# schematic_without_jumperlable.net
KiCad netlist of a schematic drawn in EAGLE
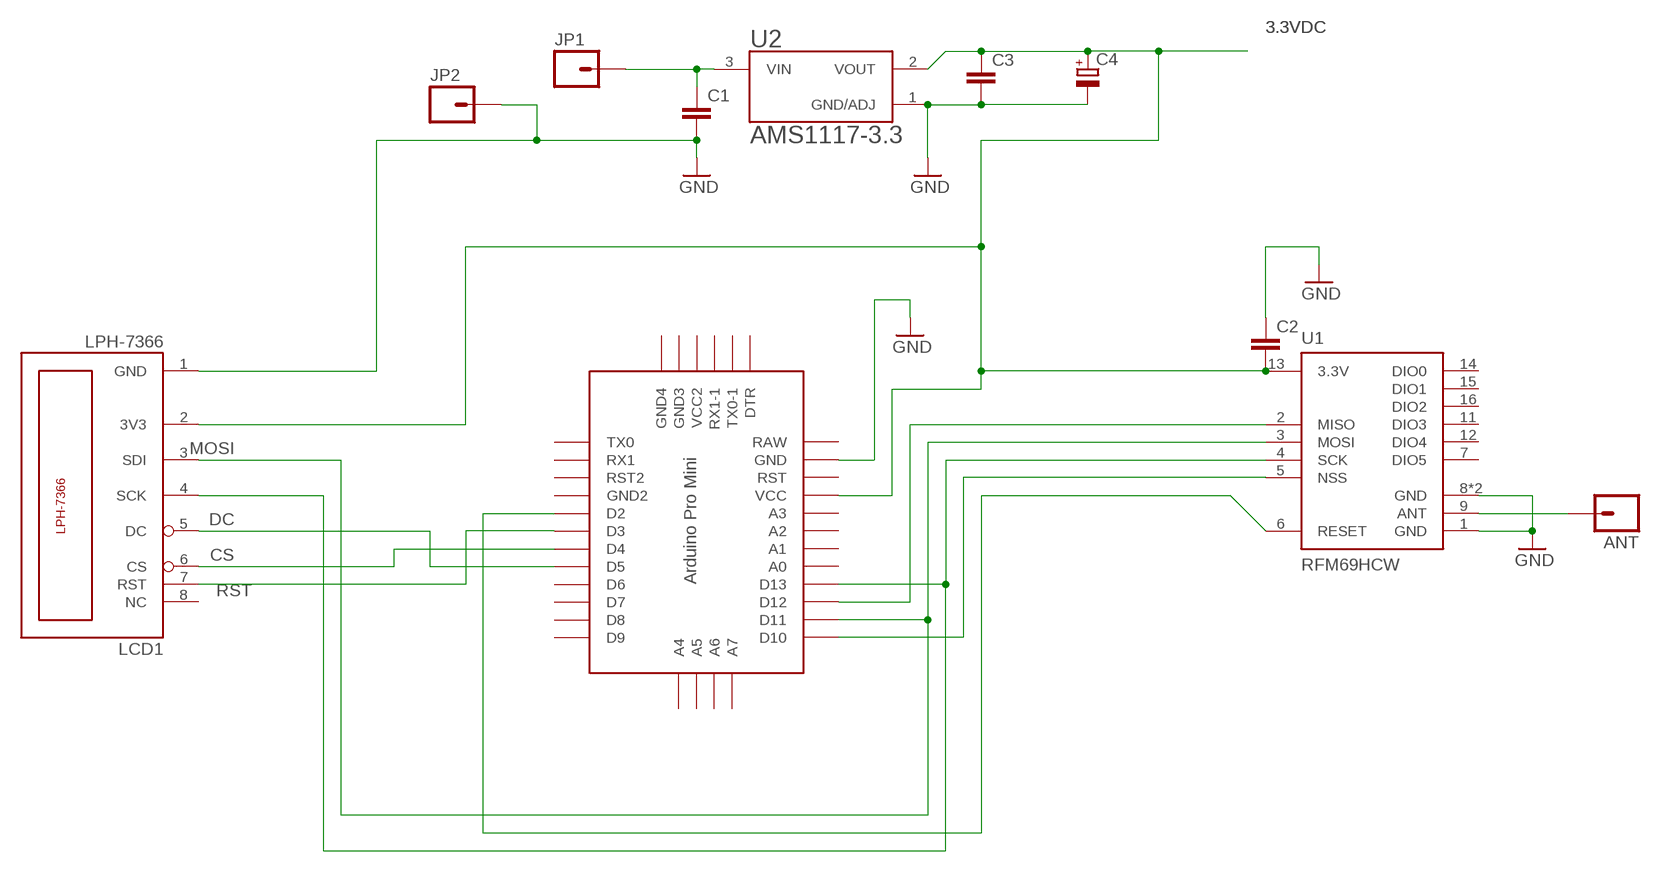
[diagram p0: schematic, sheet 1]

(export (version "E")
  (design (tool "Eeschema 10.0.6"))
  (components
    (comp (ref "ANT")
      (value "M01SMDNS")
      (footprint "eagle-import:1X01NS")
      (libsource (lib "eagle-import") (part "M01SMDNS"))
    )
    (comp (ref "C1")
      (value "C-EU025-030X050")
      (footprint "eagle-import:C025-030X050")
      (libsource (lib "eagle-import") (part "C-EU025-030X050"))
    )
    (comp (ref "C2")
      (value "C-EU025-030X050")
      (footprint "eagle-import:C025-030X050")
      (libsource (lib "eagle-import") (part "C-EU025-030X050"))
    )
    (comp (ref "C3")
      (value "C-EU025-030X050")
      (footprint "eagle-import:C025-030X050")
      (libsource (lib "eagle-import") (part "C-EU025-030X050"))
    )
    (comp (ref "C4")
      (value "CPOL-EUE5-8.5")
      (footprint "eagle-import:E5-8,5")
      (libsource (lib "eagle-import") (part "CPOL-EUE5-8.5"))
    )
    (comp (ref "JP1")
      (value "M01SMDNS")
      (footprint "eagle-import:1X01NS")
      (libsource (lib "eagle-import") (part "M01SMDNS"))
    )
    (comp (ref "JP2")
      (value "M01SMDNS")
      (footprint "eagle-import:1X01NS")
      (libsource (lib "eagle-import") (part "M01SMDNS"))
    )
    (comp (ref "LCD1")
      (value "LPH-7366")
      (footprint "eagle-import:LPH-7366")
      (libsource (lib "eagle-import") (part "LPH-7366"))
    )
    (comp (ref "U$1")
      (value "PRO-MINI")
      (footprint "eagle-import:PRO-MINI")
      (libsource (lib "eagle-import") (part "PRO-MINI"))
    )
    (comp (ref "U1")
      (value "RFM69HCW")
      (footprint "eagle-import:RFM69HCW-XXXS2")
      (libsource (lib "eagle-import") (part "RFM69HCW"))
    )
    (comp (ref "U2")
      (value "AMS1117-3.3")
      (footprint "eagle-import:SOT229P700X180-4N")
      (fields (field (name "MF") "Advanced Monolithic Systems"))
      (libsource (lib "eagle-import") (part "AMS1117-3.3"))
    )
  )
  (nets
    (net (code "1") (name "/3.3VDC") (class "Default")
      (node (ref "C2") (pin "2") (pinfunction "2_2") (pintype "passive"))
      (node (ref "C3") (pin "1") (pinfunction "1_1") (pintype "passive"))
      (node (ref "C4") (pin "+") (pinfunction "+_+") (pintype "passive"))
      (node (ref "LCD1") (pin "2") (pinfunction "3V3_2") (pintype "power_in"))
      (node (ref "U$1") (pin "VCC") (pinfunction "VCC_VCC") (pintype "bidirectional"))
      (node (ref "U1") (pin "13") (pinfunction "3.3V_13") (pintype "power_in"))
      (node (ref "U2") (pin "2") (pinfunction "VOUT_2") (pintype "output"))
    )
    (net (code "2") (name "/CS") (class "Default")
      (node (ref "LCD1") (pin "6") (pinfunction "CS_6") (pintype "input"))
      (node (ref "U$1") (pin "D4") (pinfunction "D4_D4") (pintype "bidirectional"))
    )
    (net (code "3") (name "/DC") (class "Default")
      (node (ref "LCD1") (pin "5") (pinfunction "DC_5") (pintype "input"))
      (node (ref "U$1") (pin "D5") (pinfunction "D5_D5") (pintype "bidirectional"))
    )
    (net (code "4") (name "/MOSI") (class "Default")
      (node (ref "LCD1") (pin "3") (pinfunction "SDI_3") (pintype "power_in"))
      (node (ref "U$1") (pin "D11") (pinfunction "D11_D11") (pintype "bidirectional"))
      (node (ref "U1") (pin "3") (pinfunction "MOSI_3") (pintype "input"))
    )
    (net (code "5") (name "/RAW") (class "Default")
      (node (ref "U$1") (pin "RAW") (pinfunction "RAW_RAW") (pintype "power_in"))
    )
    (net (code "6") (name "/RST") (class "Default")
      (node (ref "LCD1") (pin "7") (pinfunction "RST_7") (pintype "input"))
      (node (ref "U$1") (pin "D3") (pinfunction "D3_D3") (pintype "bidirectional"))
    )
    (net (code "7") (name "GND") (class "Default")
      (node (ref "C1") (pin "2") (pinfunction "2_2") (pintype "passive"))
      (node (ref "C2") (pin "1") (pinfunction "1_1") (pintype "passive"))
      (node (ref "C3") (pin "2") (pinfunction "2_2") (pintype "passive"))
      (node (ref "C4") (pin "-") (pinfunction "-_-") (pintype "passive"))
      (node (ref "JP2") (pin "1") (pinfunction "1_1") (pintype "passive"))
      (node (ref "LCD1") (pin "1") (pinfunction "GND_1") (pintype "power_in"))
      (node (ref "U$1") (pin "GND") (pinfunction "GND_GND") (pintype "input"))
      (node (ref "U1") (pin "1") (pinfunction "GND_1") (pintype "power_in"))
      (node (ref "U1") (pin "10") (pinfunction "GND_10") (pintype "power_in"))
      (node (ref "U1") (pin "8") (pinfunction "GND_8") (pintype "power_in"))
      (node (ref "U2") (pin "1") (pinfunction "GND/ADJ_1") (pintype "power_in"))
    )
    (net (code "8") (name "Net-(LCD1-SCK)") (class "Default")
      (node (ref "LCD1") (pin "4") (pinfunction "SCK_4") (pintype "power_in"))
      (node (ref "U$1") (pin "D13") (pinfunction "D13_D13") (pintype "bidirectional"))
      (node (ref "U1") (pin "4") (pinfunction "SCK_4") (pintype "input"))
    )
    (net (code "9") (name "Net-(U1-ANT)") (class "Default")
      (node (ref "ANT") (pin "1") (pinfunction "1_1") (pintype "passive"))
      (node (ref "U1") (pin "9") (pinfunction "ANT_9") (pintype "passive"))
    )
    (net (code "10") (name "Net-(U1-MISO)") (class "Default")
      (node (ref "U$1") (pin "D12") (pinfunction "D12_D12") (pintype "bidirectional"))
      (node (ref "U1") (pin "2") (pinfunction "MISO_2") (pintype "bidirectional"))
    )
    (net (code "11") (name "Net-(U1-NSS)") (class "Default")
      (node (ref "U$1") (pin "D10") (pinfunction "D10_D10") (pintype "bidirectional"))
      (node (ref "U1") (pin "5") (pinfunction "NSS_5") (pintype "input"))
    )
    (net (code "12") (name "Net-(U1-RESET)") (class "Default")
      (node (ref "U$1") (pin "D2") (pinfunction "D2_D2") (pintype "bidirectional"))
      (node (ref "U1") (pin "6") (pinfunction "RESET_6") (pintype "input"))
    )
    (net (code "13") (name "Net-(U2-VIN)") (class "Default")
      (node (ref "C1") (pin "1") (pinfunction "1_1") (pintype "passive"))
      (node (ref "JP1") (pin "1") (pinfunction "1_1") (pintype "passive"))
      (node (ref "U2") (pin "3") (pinfunction "VIN_3") (pintype "input"))
    )
    (net (code "14") (name "unconnected-(LCD1-NC-Pad8)") (class "Default")
      (node (ref "LCD1") (pin "8") (pinfunction "NC_8") (pintype "no_connect"))
    )
    (net (code "15") (name "unconnected-(U$1-GND2-PadGND1)") (class "Default")
      (node (ref "U$1") (pin "GND1") (pinfunction "GND2_GND1") (pintype "bidirectional"))
    )
    (net (code "16") (name "unconnected-(U$1-GND4-PadGND2)") (class "Default")
      (node (ref "U$1") (pin "GND2") (pinfunction "GND4_GND2") (pintype "bidirectional"))
    )
    (net (code "17") (name "unconnected-(U$1-PadA0)") (class "Default")
      (node (ref "U$1") (pin "A0") (pinfunction "A0_A0") (pintype "bidirectional"))
    )
    (net (code "18") (name "unconnected-(U$1-PadA1)") (class "Default")
      (node (ref "U$1") (pin "A1") (pinfunction "A1_A1") (pintype "bidirectional"))
    )
    (net (code "19") (name "unconnected-(U$1-PadA2)") (class "Default")
      (node (ref "U$1") (pin "A2") (pinfunction "A2_A2") (pintype "bidirectional"))
    )
    (net (code "20") (name "unconnected-(U$1-PadA3)") (class "Default")
      (node (ref "U$1") (pin "A3") (pinfunction "A3_A3") (pintype "bidirectional"))
    )
    (net (code "21") (name "unconnected-(U$1-PadA4)") (class "Default")
      (node (ref "U$1") (pin "A4") (pinfunction "A4_A4") (pintype "bidirectional"))
    )
    (net (code "22") (name "unconnected-(U$1-PadA5)") (class "Default")
      (node (ref "U$1") (pin "A5") (pinfunction "A5_A5") (pintype "bidirectional"))
    )
    (net (code "23") (name "unconnected-(U$1-PadA6)") (class "Default")
      (node (ref "U$1") (pin "A6") (pinfunction "A6_A6") (pintype "bidirectional"))
    )
    (net (code "24") (name "unconnected-(U$1-PadA7)") (class "Default")
      (node (ref "U$1") (pin "A7") (pinfunction "A7_A7") (pintype "bidirectional"))
    )
    (net (code "25") (name "unconnected-(U$1-PadD6)") (class "Default")
      (node (ref "U$1") (pin "D6") (pinfunction "D6_D6") (pintype "bidirectional"))
    )
    (net (code "26") (name "unconnected-(U$1-PadD7)") (class "Default")
      (node (ref "U$1") (pin "D7") (pinfunction "D7_D7") (pintype "bidirectional"))
    )
    (net (code "27") (name "unconnected-(U$1-PadD8)") (class "Default")
      (node (ref "U$1") (pin "D8") (pinfunction "D8_D8") (pintype "bidirectional"))
    )
    (net (code "28") (name "unconnected-(U$1-PadD9)") (class "Default")
      (node (ref "U$1") (pin "D9") (pinfunction "D9_D9") (pintype "bidirectional"))
    )
    (net (code "29") (name "unconnected-(U$1-PadDTR)") (class "Default")
      (node (ref "U$1") (pin "DTR") (pinfunction "DTR_DTR") (pintype "bidirectional"))
    )
    (net (code "30") (name "unconnected-(U$1-PadGND3)") (class "Default")
      (node (ref "U$1") (pin "GND3") (pinfunction "GND3_GND3") (pintype "bidirectional"))
    )
    (net (code "31") (name "unconnected-(U$1-PadRST)") (class "Default")
      (node (ref "U$1") (pin "RST") (pinfunction "RST_RST") (pintype "bidirectional"))
    )
    (net (code "32") (name "unconnected-(U$1-PadRX1)") (class "Default")
      (node (ref "U$1") (pin "RX1") (pinfunction "RX1_RX1") (pintype "bidirectional"))
    )
    (net (code "33") (name "unconnected-(U$1-PadRX1-1)") (class "Default")
      (node (ref "U$1") (pin "RX1-1") (pinfunction "RX1-1_RX1-1") (pintype "bidirectional"))
    )
    (net (code "34") (name "unconnected-(U$1-PadTX0)") (class "Default")
      (node (ref "U$1") (pin "TX0") (pinfunction "TX0_TX0") (pintype "bidirectional"))
    )
    (net (code "35") (name "unconnected-(U$1-PadTX0-1)") (class "Default")
      (node (ref "U$1") (pin "TX0-1") (pinfunction "TX0-1_TX0-1") (pintype "bidirectional"))
    )
    (net (code "36") (name "unconnected-(U$1-RST2-PadRST1)") (class "Default")
      (node (ref "U$1") (pin "RST1") (pinfunction "RST2_RST1") (pintype "bidirectional"))
    )
    (net (code "37") (name "unconnected-(U$1-VCC2-PadVCC1)") (class "Default")
      (node (ref "U$1") (pin "VCC1") (pinfunction "VCC2_VCC1") (pintype "bidirectional"))
    )
    (net (code "38") (name "unconnected-(U1-DIO0-Pad14)") (class "Default")
      (node (ref "U1") (pin "14") (pinfunction "DIO0_14") (pintype "bidirectional"))
    )
    (net (code "39") (name "unconnected-(U1-DIO1-Pad15)") (class "Default")
      (node (ref "U1") (pin "15") (pinfunction "DIO1_15") (pintype "bidirectional"))
    )
    (net (code "40") (name "unconnected-(U1-DIO2-Pad16)") (class "Default")
      (node (ref "U1") (pin "16") (pinfunction "DIO2_16") (pintype "bidirectional"))
    )
    (net (code "41") (name "unconnected-(U1-DIO3-Pad11)") (class "Default")
      (node (ref "U1") (pin "11") (pinfunction "DIO3_11") (pintype "bidirectional"))
    )
    (net (code "42") (name "unconnected-(U1-DIO4-Pad12)") (class "Default")
      (node (ref "U1") (pin "12") (pinfunction "DIO4_12") (pintype "bidirectional"))
    )
    (net (code "43") (name "unconnected-(U1-DIO5-Pad7)") (class "Default")
      (node (ref "U1") (pin "7") (pinfunction "DIO5_7") (pintype "bidirectional"))
    )
  )
)
